# schematic.net
KiCad netlist of a schematic drawn in EAGLE
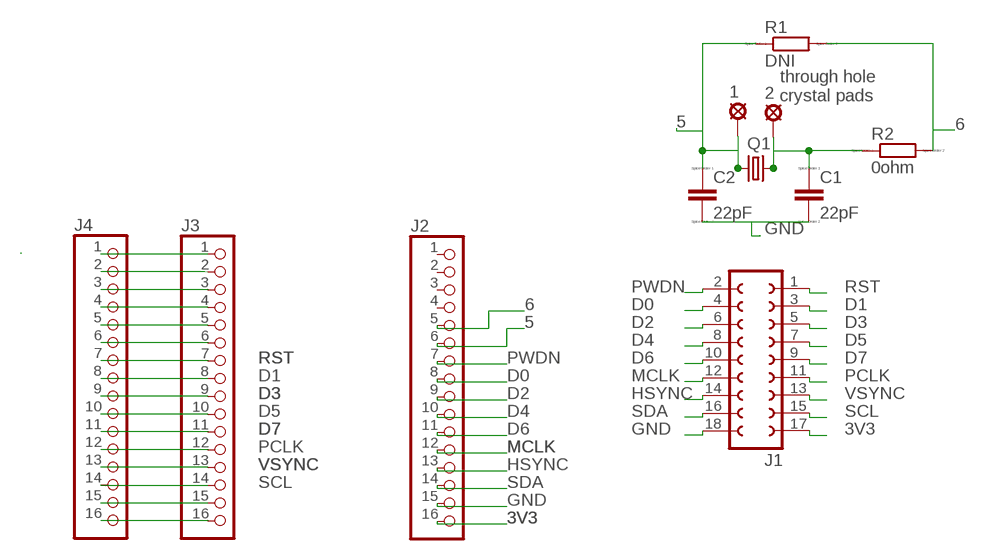
[diagram p0: schematic, sheet 1]

(export (version "E")
  (design (tool "Eeschema 10.0.6"))
  (components
    (comp (ref "1")
      (value "LSP10")
      (footprint "eagle-import:LSP10")
      (libsource (lib "eagle-import") (part "LSP10"))
    )
    (comp (ref "2")
      (value "LSP10")
      (footprint "eagle-import:LSP10")
      (libsource (lib "eagle-import") (part "LSP10"))
    )
    (comp (ref "C1")
      (value "22pF")
      (footprint "eagle-import:C0603")
      (libsource (lib "eagle-import") (part "CC0603"))
    )
    (comp (ref "C2")
      (value "22pF")
      (footprint "eagle-import:C0603")
      (libsource (lib "eagle-import") (part "CC0603"))
    )
    (comp (ref "J1")
      (value "FE09-2")
      (footprint "eagle-import:FE09-2")
      (libsource (lib "eagle-import") (part "FE09-2"))
    )
    (comp (ref "J2")
      (value "PINHD-1X16")
      (footprint "eagle-import:1X16")
      (libsource (lib "eagle-import") (part "PINHD-1X16"))
    )
    (comp (ref "J3")
      (value "PINHD-1X16")
      (footprint "eagle-import:1X16")
      (libsource (lib "eagle-import") (part "PINHD-1X16"))
    )
    (comp (ref "J4")
      (value "PINHD-1X16")
      (footprint "eagle-import:1X16")
      (libsource (lib "eagle-import") (part "PINHD-1X16"))
    )
    (comp (ref "Q1")
      (value "CRYSTALHC49UP")
      (footprint "eagle-import:HC49UP")
      (libsource (lib "eagle-import") (part "CRYSTALHC49UP"))
    )
    (comp (ref "R1")
      (value "DNI")
      (footprint "eagle-import:R0603")
      (libsource (lib "eagle-import") (part "RR0603"))
    )
    (comp (ref "R2")
      (value "0ohm")
      (footprint "eagle-import:R0603")
      (libsource (lib "eagle-import") (part "RR0603"))
    )
  )
  (nets
    (net (code "1") (name "/3V3") (class "Default")
      (node (ref "J1") (pin "17") (pinfunction "17_17") (pintype "passive"))
      (node (ref "J2") (pin "16") (pinfunction "16_16") (pintype "passive"))
    )
    (net (code "2") (name "/5") (class "Default")
      (node (ref "1") (pin "MP") (pinfunction "MP_MP") (pintype "passive"))
      (node (ref "C2") (pin "1") (pinfunction "1_1") (pintype "passive"))
      (node (ref "J2") (pin "6") (pinfunction "6_6") (pintype "passive"))
      (node (ref "Q1") (pin "1") (pinfunction "1_1") (pintype "passive"))
      (node (ref "R1") (pin "1") (pinfunction "1_1") (pintype "passive"))
    )
    (net (code "3") (name "/6") (class "Default")
      (node (ref "J2") (pin "5") (pinfunction "5_5") (pintype "passive"))
      (node (ref "R1") (pin "2") (pinfunction "2_2") (pintype "passive"))
      (node (ref "R2") (pin "2") (pinfunction "2_2") (pintype "passive"))
    )
    (net (code "4") (name "/D0") (class "Default")
      (node (ref "J1") (pin "4") (pinfunction "4_4") (pintype "passive"))
      (node (ref "J2") (pin "8") (pinfunction "8_8") (pintype "passive"))
    )
    (net (code "5") (name "/D1") (class "Default")
      (node (ref "J1") (pin "3") (pinfunction "3_3") (pintype "passive"))
      (node (ref "J3") (pin "8") (pinfunction "8_8") (pintype "passive"))
      (node (ref "J4") (pin "8") (pinfunction "8_8") (pintype "passive"))
    )
    (net (code "6") (name "/D2") (class "Default")
      (node (ref "J1") (pin "6") (pinfunction "6_6") (pintype "passive"))
      (node (ref "J2") (pin "9") (pinfunction "9_9") (pintype "passive"))
    )
    (net (code "7") (name "/D3") (class "Default")
      (node (ref "J1") (pin "5") (pinfunction "5_5") (pintype "passive"))
      (node (ref "J3") (pin "9") (pinfunction "9_9") (pintype "passive"))
      (node (ref "J4") (pin "9") (pinfunction "9_9") (pintype "passive"))
    )
    (net (code "8") (name "/D4") (class "Default")
      (node (ref "J1") (pin "8") (pinfunction "8_8") (pintype "passive"))
      (node (ref "J2") (pin "10") (pinfunction "10_10") (pintype "passive"))
    )
    (net (code "9") (name "/D5") (class "Default")
      (node (ref "J1") (pin "7") (pinfunction "7_7") (pintype "passive"))
      (node (ref "J3") (pin "10") (pinfunction "10_10") (pintype "passive"))
      (node (ref "J4") (pin "10") (pinfunction "10_10") (pintype "passive"))
    )
    (net (code "10") (name "/D6") (class "Default")
      (node (ref "J1") (pin "10") (pinfunction "10_10") (pintype "passive"))
      (node (ref "J2") (pin "11") (pinfunction "11_11") (pintype "passive"))
    )
    (net (code "11") (name "/D7") (class "Default")
      (node (ref "J1") (pin "9") (pinfunction "9_9") (pintype "passive"))
      (node (ref "J3") (pin "11") (pinfunction "11_11") (pintype "passive"))
      (node (ref "J4") (pin "11") (pinfunction "11_11") (pintype "passive"))
    )
    (net (code "12") (name "/GND") (class "Default")
      (node (ref "C1") (pin "2") (pinfunction "2_2") (pintype "passive"))
      (node (ref "C2") (pin "2") (pinfunction "2_2") (pintype "passive"))
      (node (ref "J1") (pin "18") (pinfunction "18_18") (pintype "passive"))
      (node (ref "J2") (pin "15") (pinfunction "15_15") (pintype "passive"))
    )
    (net (code "13") (name "/HSYNC") (class "Default")
      (node (ref "J1") (pin "14") (pinfunction "14_14") (pintype "passive"))
      (node (ref "J2") (pin "13") (pinfunction "13_13") (pintype "passive"))
    )
    (net (code "14") (name "/MCLK") (class "Default")
      (node (ref "J1") (pin "12") (pinfunction "12_12") (pintype "passive"))
      (node (ref "J2") (pin "12") (pinfunction "12_12") (pintype "passive"))
    )
    (net (code "15") (name "/PCLK") (class "Default")
      (node (ref "J1") (pin "11") (pinfunction "11_11") (pintype "passive"))
      (node (ref "J3") (pin "12") (pinfunction "12_12") (pintype "passive"))
      (node (ref "J4") (pin "12") (pinfunction "12_12") (pintype "passive"))
    )
    (net (code "16") (name "/PWDN") (class "Default")
      (node (ref "J1") (pin "2") (pinfunction "2_2") (pintype "passive"))
      (node (ref "J2") (pin "7") (pinfunction "7_7") (pintype "passive"))
    )
    (net (code "17") (name "/RST") (class "Default")
      (node (ref "J1") (pin "1") (pinfunction "1_1") (pintype "passive"))
      (node (ref "J3") (pin "7") (pinfunction "7_7") (pintype "passive"))
      (node (ref "J4") (pin "7") (pinfunction "7_7") (pintype "passive"))
    )
    (net (code "18") (name "/SCL") (class "Default")
      (node (ref "J1") (pin "15") (pinfunction "15_15") (pintype "passive"))
      (node (ref "J3") (pin "14") (pinfunction "14_14") (pintype "passive"))
      (node (ref "J4") (pin "14") (pinfunction "14_14") (pintype "passive"))
    )
    (net (code "19") (name "/SDA") (class "Default")
      (node (ref "J1") (pin "16") (pinfunction "16_16") (pintype "passive"))
      (node (ref "J2") (pin "14") (pinfunction "14_14") (pintype "passive"))
    )
    (net (code "20") (name "/VSYNC") (class "Default")
      (node (ref "J1") (pin "13") (pinfunction "13_13") (pintype "passive"))
      (node (ref "J3") (pin "13") (pinfunction "13_13") (pintype "passive"))
      (node (ref "J4") (pin "13") (pinfunction "13_13") (pintype "passive"))
    )
    (net (code "21") (name "Net-(2-PadMP)") (class "Default")
      (node (ref "2") (pin "MP") (pinfunction "MP_MP") (pintype "passive"))
      (node (ref "C1") (pin "1") (pinfunction "1_1") (pintype "passive"))
      (node (ref "Q1") (pin "2") (pinfunction "2_2") (pintype "passive"))
      (node (ref "R2") (pin "1") (pinfunction "1_1") (pintype "passive"))
    )
    (net (code "22") (name "Net-(J3-Pad1)") (class "Default")
      (node (ref "J3") (pin "1") (pinfunction "1_1") (pintype "passive"))
      (node (ref "J4") (pin "1") (pinfunction "1_1") (pintype "passive"))
    )
    (net (code "23") (name "Net-(J3-Pad2)") (class "Default")
      (node (ref "J3") (pin "2") (pinfunction "2_2") (pintype "passive"))
      (node (ref "J4") (pin "2") (pinfunction "2_2") (pintype "passive"))
    )
    (net (code "24") (name "Net-(J3-Pad3)") (class "Default")
      (node (ref "J3") (pin "3") (pinfunction "3_3") (pintype "passive"))
      (node (ref "J4") (pin "3") (pinfunction "3_3") (pintype "passive"))
    )
    (net (code "25") (name "Net-(J3-Pad4)") (class "Default")
      (node (ref "J3") (pin "4") (pinfunction "4_4") (pintype "passive"))
      (node (ref "J4") (pin "4") (pinfunction "4_4") (pintype "passive"))
    )
    (net (code "26") (name "Net-(J3-Pad5)") (class "Default")
      (node (ref "J3") (pin "5") (pinfunction "5_5") (pintype "passive"))
      (node (ref "J4") (pin "5") (pinfunction "5_5") (pintype "passive"))
    )
    (net (code "27") (name "Net-(J3-Pad6)") (class "Default")
      (node (ref "J3") (pin "6") (pinfunction "6_6") (pintype "passive"))
      (node (ref "J4") (pin "6") (pinfunction "6_6") (pintype "passive"))
    )
    (net (code "28") (name "Net-(J3-Pad15)") (class "Default")
      (node (ref "J3") (pin "15") (pinfunction "15_15") (pintype "passive"))
      (node (ref "J4") (pin "15") (pinfunction "15_15") (pintype "passive"))
    )
    (net (code "29") (name "Net-(J3-Pad16)") (class "Default")
      (node (ref "J3") (pin "16") (pinfunction "16_16") (pintype "passive"))
      (node (ref "J4") (pin "16") (pinfunction "16_16") (pintype "passive"))
    )
    (net (code "30") (name "unconnected-(J2-Pad1)") (class "Default")
      (node (ref "J2") (pin "1") (pinfunction "1_1") (pintype "passive"))
    )
    (net (code "31") (name "unconnected-(J2-Pad2)") (class "Default")
      (node (ref "J2") (pin "2") (pinfunction "2_2") (pintype "passive"))
    )
    (net (code "32") (name "unconnected-(J2-Pad3)") (class "Default")
      (node (ref "J2") (pin "3") (pinfunction "3_3") (pintype "passive"))
    )
    (net (code "33") (name "unconnected-(J2-Pad4)") (class "Default")
      (node (ref "J2") (pin "4") (pinfunction "4_4") (pintype "passive"))
    )
  )
)
